# DCTCXO.net
KiCad netlist of a schematic drawn in Altium Designer
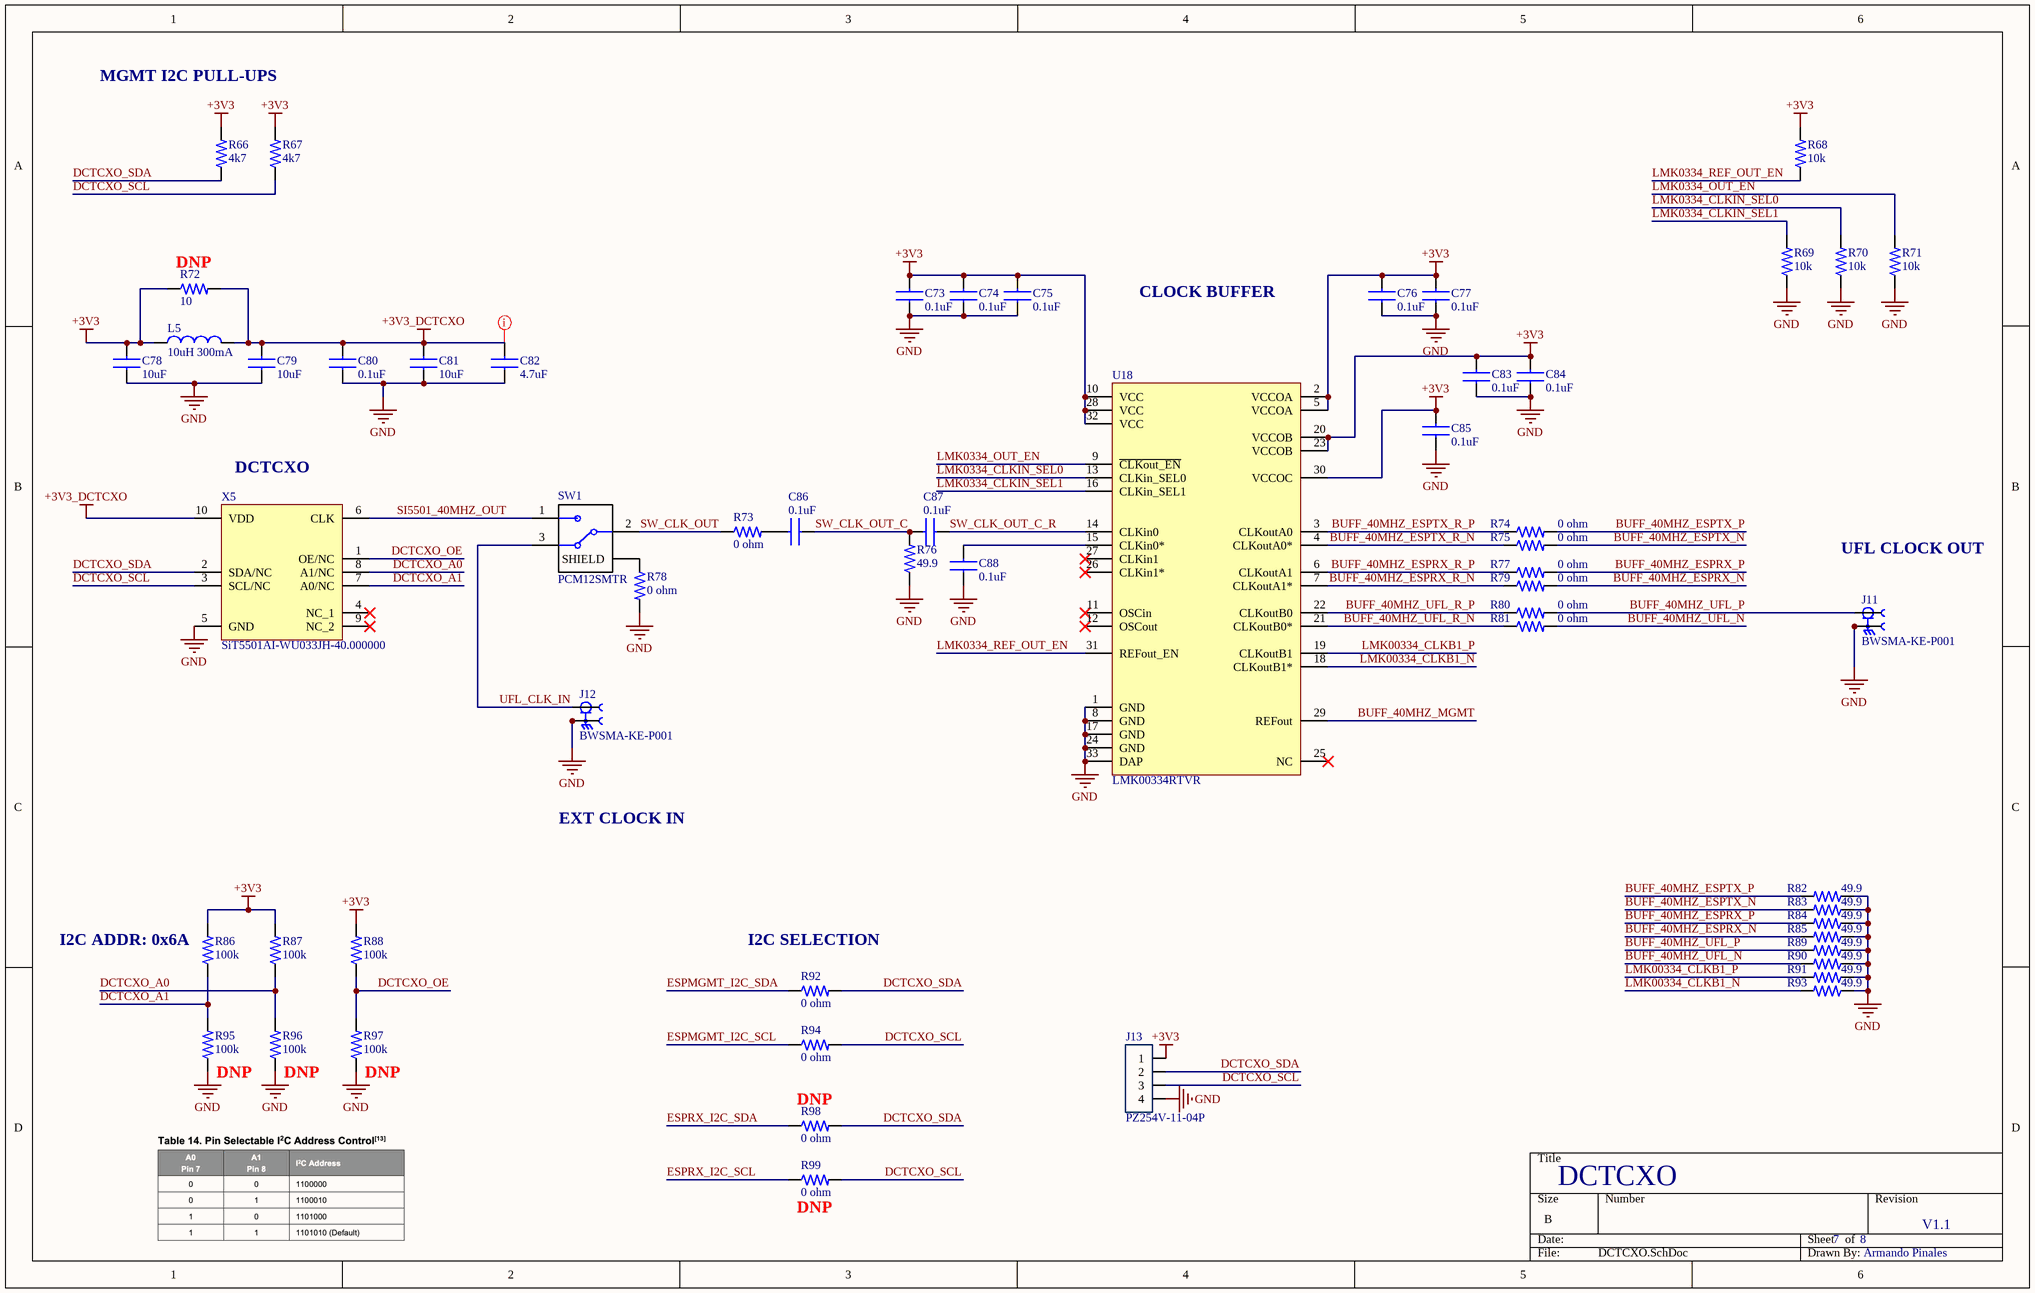
[diagram p0: DCTCXO.SchDoc]

(export (version "E")
  (design (tool "Eeschema 10.0.6"))
  (components
    (comp (ref "C73")
      (value "0.1uF")
      (footprint "CAP_0402")
      (description "Cap Ceramic 0.1uF 16V X7R 10% SMD 0402 125C Paper T/R")
      (fields
        (field (name "MANUFACTURER") "Murata")
        (field (name "MANUFACTURER PART NUMBER") "GCM155R71C104KA55J")
      )
      (libsource (lib "LotusSound") (part "CAP_GCM155R71C104KA55J"))
    )
    (comp (ref "C74")
      (value "0.1uF")
      (footprint "CAP_0402")
      (description "Cap Ceramic 0.1uF 16V X7R 10% SMD 0402 125C Paper T/R")
      (fields
        (field (name "MANUFACTURER") "Murata")
        (field (name "MANUFACTURER PART NUMBER") "GCM155R71C104KA55J")
      )
      (libsource (lib "LotusSound") (part "CAP_GCM155R71C104KA55J"))
    )
    (comp (ref "C75")
      (value "0.1uF")
      (footprint "CAP_0402")
      (description "Cap Ceramic 0.1uF 16V X7R 10% SMD 0402 125C Paper T/R")
      (fields
        (field (name "MANUFACTURER") "Murata")
        (field (name "MANUFACTURER PART NUMBER") "GCM155R71C104KA55J")
      )
      (libsource (lib "LotusSound") (part "CAP_GCM155R71C104KA55J"))
    )
    (comp (ref "C76")
      (value "0.1uF")
      (footprint "CAP_0402")
      (description "Cap Ceramic 0.1uF 16V X7R 10% SMD 0402 125C Paper T/R")
      (fields
        (field (name "MANUFACTURER") "Murata")
        (field (name "MANUFACTURER PART NUMBER") "GCM155R71C104KA55J")
      )
      (libsource (lib "LotusSound") (part "CAP_GCM155R71C104KA55J"))
    )
    (comp (ref "C77")
      (value "0.1uF")
      (footprint "CAP_0402")
      (description "Cap Ceramic 0.1uF 16V X7R 10% SMD 0402 125C Paper T/R")
      (fields
        (field (name "MANUFACTURER") "Murata")
        (field (name "MANUFACTURER PART NUMBER") "GCM155R71C104KA55J")
      )
      (libsource (lib "LotusSound") (part "CAP_GCM155R71C104KA55J"))
    )
    (comp (ref "C78")
      (value "10uF")
      (footprint "CAP_0402")
      (description "Cap Ceramic 10uF 6.3V X5R 20% SMD 0402 85°C Paper T/R")
      (fields
        (field (name "MANUFACTURER") "Samsung")
        (field (name "MANUFACTURER PART NUMBER") "CL05A106MQ5NUNC")
      )
      (libsource (lib "LotusSound") (part "CAP_CL05A106MQ5NUNC"))
    )
    (comp (ref "C79")
      (value "10uF")
      (footprint "CAP_0402")
      (description "Cap Ceramic 10uF 6.3V X5R 20% SMD 0402 85°C Paper T/R")
      (fields
        (field (name "MANUFACTURER") "Samsung")
        (field (name "MANUFACTURER PART NUMBER") "CL05A106MQ5NUNC")
      )
      (libsource (lib "LotusSound") (part "CAP_CL05A106MQ5NUNC"))
    )
    (comp (ref "C80")
      (value "0.1uF")
      (footprint "CAP_0402")
      (description "Cap Ceramic 0.1uF 16V X7R 10% SMD 0402 125C Paper T/R")
      (fields
        (field (name "MANUFACTURER") "Murata")
        (field (name "MANUFACTURER PART NUMBER") "GCM155R71C104KA55J")
      )
      (libsource (lib "LotusSound") (part "CAP_GCM155R71C104KA55J"))
    )
    (comp (ref "C81")
      (value "10uF")
      (footprint "CAP_0402")
      (description "Cap Ceramic 10uF 6.3V X5R 20% SMD 0402 85°C Paper T/R")
      (fields
        (field (name "MANUFACTURER") "Samsung")
        (field (name "MANUFACTURER PART NUMBER") "CL05A106MQ5NUNC")
      )
      (libsource (lib "LotusSound") (part "CAP_CL05A106MQ5NUNC"))
    )
    (comp (ref "C82")
      (value "4.7uF")
      (footprint "CAP_0402")
      (description "Multilayer Ceramic Capacitors MLCC - SMD/SMT 4.7uF 10V X5R +/-20% 0402 Gen Purp")
      (fields
        (field (name "MANUFACTURER") "Taiyo Yuden")
        (field (name "MANUFACTURER PART NUMBER") "LMK105BBJ475MVLF")
      )
      (libsource (lib "LotusSound") (part "CAP_LMK105BBJ475MVLF"))
    )
    (comp (ref "C83")
      (value "0.1uF")
      (footprint "CAP_0402")
      (description "Cap Ceramic 0.1uF 16V X7R 10% SMD 0402 125C Paper T/R")
      (fields
        (field (name "MANUFACTURER") "Murata")
        (field (name "MANUFACTURER PART NUMBER") "GCM155R71C104KA55J")
      )
      (libsource (lib "LotusSound") (part "CAP_GCM155R71C104KA55J"))
    )
    (comp (ref "C84")
      (value "0.1uF")
      (footprint "CAP_0402")
      (description "Cap Ceramic 0.1uF 16V X7R 10% SMD 0402 125C Paper T/R")
      (fields
        (field (name "MANUFACTURER") "Murata")
        (field (name "MANUFACTURER PART NUMBER") "GCM155R71C104KA55J")
      )
      (libsource (lib "LotusSound") (part "CAP_GCM155R71C104KA55J"))
    )
    (comp (ref "C85")
      (value "0.1uF")
      (footprint "CAP_0402")
      (description "Cap Ceramic 0.1uF 16V X7R 10% SMD 0402 125C Paper T/R")
      (fields
        (field (name "MANUFACTURER") "Murata")
        (field (name "MANUFACTURER PART NUMBER") "GCM155R71C104KA55J")
      )
      (libsource (lib "LotusSound") (part "CAP_GCM155R71C104KA55J"))
    )
    (comp (ref "C86")
      (value "0.1uF")
      (footprint "CAP_0402")
      (description "Cap Ceramic 0.1uF 16V X7R 10% SMD 0402 125C Paper T/R")
      (fields
        (field (name "MANUFACTURER") "Murata")
        (field (name "MANUFACTURER PART NUMBER") "GCM155R71C104KA55J")
      )
      (libsource (lib "LotusSound") (part "CAP_GCM155R71C104KA55J"))
    )
    (comp (ref "C87")
      (value "0.1uF")
      (footprint "CAP_0402")
      (description "Cap Ceramic 0.1uF 16V X7R 10% SMD 0402 125C Paper T/R")
      (fields
        (field (name "MANUFACTURER") "Murata")
        (field (name "MANUFACTURER PART NUMBER") "GCM155R71C104KA55J")
      )
      (libsource (lib "LotusSound") (part "CAP_GCM155R71C104KA55J"))
    )
    (comp (ref "C88")
      (value "0.1uF")
      (footprint "CAP_0402")
      (description "Cap Ceramic 0.1uF 16V X7R 10% SMD 0402 125C Paper T/R")
      (fields
        (field (name "MANUFACTURER") "Murata")
        (field (name "MANUFACTURER PART NUMBER") "GCM155R71C104KA55J")
      )
      (libsource (lib "LotusSound") (part "CAP_GCM155R71C104KA55J"))
    )
    (comp (ref "J11")
      (value "BWSMA-KE-P001")
      (footprint "CONN_BWSMA-KE-P001")
      (description "0-12.4GHz 50Ω 335V 直插偏脚")
      (fields (field (name "MANUFACTURER") "BAT Wireless"))
      (libsource (lib "LotusSound") (part "CONN_BWSMA-KE-P001"))
    )
    (comp (ref "J12")
      (value "BWSMA-KE-P001")
      (footprint "CONN_BWSMA-KE-P001")
      (description "0-12.4GHz 50Ω 335V 直插偏脚")
      (fields (field (name "MANUFACTURER") "BAT Wireless"))
      (libsource (lib "LotusSound") (part "CONN_BWSMA-KE-P001"))
    )
    (comp (ref "J13")
      (value "PZ254V-11-04P")
      (footprint "CONN_4_PIN_M_100MIL")
      (description "单排排针 间距2.54mm 4pin 直插")
      (fields (field (name "MANUFACTURER") "XFCN"))
      (libsource (lib "LotusSound") (part "CONN_4_PIN_MALE_PZ254V-11-04P"))
    )
    (comp (ref "L5")
      (value "10uH 300mA")
      (footprint "L_490-LQM18DN100M70LCT-ND")
      (description "Inductor, 10Uh, 0.3A, Multilayer Rohs Compliant: Yes")
      (fields
        (field (name "MANUFACTURER") "Murata")
        (field (name "MANUFACTURER PART NUMBER") "LQM18DN100M70L")
      )
      (libsource (lib "LotusSound") (part "L_LQM18DN100M70L"))
    )
    (comp (ref "R66")
      (value "4k7")
      (footprint "RES_0402")
      (description "Res General Purpose Thick Film 0402 4.7K Ohm 5% 1/16W ±100ppm/°C Molded SMD Paper T/R")
      (fields
        (field (name "MANUFACTURER") "Yageo")
        (field (name "MANUFACTURER PART NUMBER") "RC0402JR-074K7L")
      )
      (libsource (lib "LotusSound") (part "RES_RC0402JR-074K7L"))
    )
    (comp (ref "R67")
      (value "4k7")
      (footprint "RES_0402")
      (description "Res General Purpose Thick Film 0402 4.7K Ohm 5% 1/16W ±100ppm/°C Molded SMD Paper T/R")
      (fields
        (field (name "MANUFACTURER") "Yageo")
        (field (name "MANUFACTURER PART NUMBER") "RC0402JR-074K7L")
      )
      (libsource (lib "LotusSound") (part "RES_RC0402JR-074K7L"))
    )
    (comp (ref "R68")
      (value "10k")
      (footprint "RES_0402")
      (description "RES SMD 10K OHM 1% 1/16W 0402")
      (fields
        (field (name "MANUFACTURER") "Yageo")
        (field (name "MANUFACTURER PART NUMBER") "AC0402FR-0710KL")
      )
      (libsource (lib "LotusSound") (part "RES_AC0402FR-0710KL"))
    )
    (comp (ref "R69")
      (value "10k")
      (footprint "RES_0402")
      (description "RES SMD 10K OHM 1% 1/16W 0402")
      (fields
        (field (name "MANUFACTURER") "Yageo")
        (field (name "MANUFACTURER PART NUMBER") "AC0402FR-0710KL")
      )
      (libsource (lib "LotusSound") (part "RES_AC0402FR-0710KL"))
    )
    (comp (ref "R70")
      (value "10k")
      (footprint "RES_0402")
      (description "RES SMD 10K OHM 1% 1/16W 0402")
      (fields
        (field (name "MANUFACTURER") "Yageo")
        (field (name "MANUFACTURER PART NUMBER") "AC0402FR-0710KL")
      )
      (libsource (lib "LotusSound") (part "RES_AC0402FR-0710KL"))
    )
    (comp (ref "R71")
      (value "10k")
      (footprint "RES_0402")
      (description "RES SMD 10K OHM 1% 1/16W 0402")
      (fields
        (field (name "MANUFACTURER") "Yageo")
        (field (name "MANUFACTURER PART NUMBER") "AC0402FR-0710KL")
      )
      (libsource (lib "LotusSound") (part "RES_AC0402FR-0710KL"))
    )
    (comp (ref "R72")
      (value "10")
      (footprint "RES_0402")
      (description "Res General Purpose Thick Film 0402 10 Ohm 1% 1/16W ±200ppm/°C Molded SMD Paper T/R")
      (fields
        (field (name "MANUFACTURER") "Yageo")
        (field (name "MANUFACTURER PART NUMBER") "RC0402FR-0710RL")
      )
      (libsource (lib "LotusSound") (part "RES_RC0402FR-0710RL"))
    )
    (comp (ref "R73")
      (value "0 ohm")
      (footprint "RES_0402")
      (description "RES SMD 0 OHM JUMPER 1/16W 0402")
      (fields
        (field (name "MANUFACTURER") "Yageo")
        (field (name "MANUFACTURER PART NUMBER") "RC0402JR-070RL")
      )
      (libsource (lib "LotusSound") (part "RES_RC0402JR-070RL"))
    )
    (comp (ref "R74")
      (value "0 ohm")
      (footprint "RES_0402")
      (description "RES SMD 0 OHM JUMPER 1/16W 0402")
      (fields
        (field (name "MANUFACTURER") "Yageo")
        (field (name "MANUFACTURER PART NUMBER") "RC0402JR-070RL")
      )
      (libsource (lib "LotusSound") (part "RES_RC0402JR-070RL"))
    )
    (comp (ref "R75")
      (value "0 ohm")
      (footprint "RES_0402")
      (description "RES SMD 0 OHM JUMPER 1/16W 0402")
      (fields
        (field (name "MANUFACTURER") "Yageo")
        (field (name "MANUFACTURER PART NUMBER") "RC0402JR-070RL")
      )
      (libsource (lib "LotusSound") (part "RES_RC0402JR-070RL"))
    )
    (comp (ref "R76")
      (value "49.9")
      (footprint "RES_0402")
      (description "Res General Purpose Thick Film 0402 49.9 Ohm 1% 1/16W ±100ppm/°C Molded SMD Paper T/R")
      (fields
        (field (name "MANUFACTURER") "Yageo")
        (field (name "MANUFACTURER PART NUMBER") "RC0402FR-0749R9L")
      )
      (libsource (lib "LotusSound") (part "RES_RC0402FR-0749R9L"))
    )
    (comp (ref "R77")
      (value "0 ohm")
      (footprint "RES_0402")
      (description "RES SMD 0 OHM JUMPER 1/16W 0402")
      (fields
        (field (name "MANUFACTURER") "Yageo")
        (field (name "MANUFACTURER PART NUMBER") "RC0402JR-070RL")
      )
      (libsource (lib "LotusSound") (part "RES_RC0402JR-070RL"))
    )
    (comp (ref "R78")
      (value "0 ohm")
      (footprint "RES_0402")
      (description "RES SMD 0 OHM JUMPER 1/16W 0402")
      (fields
        (field (name "MANUFACTURER") "Yageo")
        (field (name "MANUFACTURER PART NUMBER") "RC0402JR-070RL")
      )
      (libsource (lib "LotusSound") (part "RES_RC0402JR-070RL"))
    )
    (comp (ref "R79")
      (value "0 ohm")
      (footprint "RES_0402")
      (description "RES SMD 0 OHM JUMPER 1/16W 0402")
      (fields
        (field (name "MANUFACTURER") "Yageo")
        (field (name "MANUFACTURER PART NUMBER") "RC0402JR-070RL")
      )
      (libsource (lib "LotusSound") (part "RES_RC0402JR-070RL"))
    )
    (comp (ref "R80")
      (value "0 ohm")
      (footprint "RES_0402")
      (description "RES SMD 0 OHM JUMPER 1/16W 0402")
      (fields
        (field (name "MANUFACTURER") "Yageo")
        (field (name "MANUFACTURER PART NUMBER") "RC0402JR-070RL")
      )
      (libsource (lib "LotusSound") (part "RES_RC0402JR-070RL"))
    )
    (comp (ref "R81")
      (value "0 ohm")
      (footprint "RES_0402")
      (description "RES SMD 0 OHM JUMPER 1/16W 0402")
      (fields
        (field (name "MANUFACTURER") "Yageo")
        (field (name "MANUFACTURER PART NUMBER") "RC0402JR-070RL")
      )
      (libsource (lib "LotusSound") (part "RES_RC0402JR-070RL"))
    )
    (comp (ref "R82")
      (value "49.9")
      (footprint "RES_0402")
      (description "Res General Purpose Thick Film 0402 49.9 Ohm 1% 1/16W ±100ppm/°C Molded SMD Paper T/R")
      (fields
        (field (name "MANUFACTURER") "Yageo")
        (field (name "MANUFACTURER PART NUMBER") "RC0402FR-0749R9L")
      )
      (libsource (lib "LotusSound") (part "RES_RC0402FR-0749R9L"))
    )
    (comp (ref "R83")
      (value "49.9")
      (footprint "RES_0402")
      (description "Res General Purpose Thick Film 0402 49.9 Ohm 1% 1/16W ±100ppm/°C Molded SMD Paper T/R")
      (fields
        (field (name "MANUFACTURER") "Yageo")
        (field (name "MANUFACTURER PART NUMBER") "RC0402FR-0749R9L")
      )
      (libsource (lib "LotusSound") (part "RES_RC0402FR-0749R9L"))
    )
    (comp (ref "R84")
      (value "49.9")
      (footprint "RES_0402")
      (description "Res General Purpose Thick Film 0402 49.9 Ohm 1% 1/16W ±100ppm/°C Molded SMD Paper T/R")
      (fields
        (field (name "MANUFACTURER") "Yageo")
        (field (name "MANUFACTURER PART NUMBER") "RC0402FR-0749R9L")
      )
      (libsource (lib "LotusSound") (part "RES_RC0402FR-0749R9L"))
    )
    (comp (ref "R85")
      (value "49.9")
      (footprint "RES_0402")
      (description "Res General Purpose Thick Film 0402 49.9 Ohm 1% 1/16W ±100ppm/°C Molded SMD Paper T/R")
      (fields
        (field (name "MANUFACTURER") "Yageo")
        (field (name "MANUFACTURER PART NUMBER") "RC0402FR-0749R9L")
      )
      (libsource (lib "LotusSound") (part "RES_RC0402FR-0749R9L"))
    )
    (comp (ref "R86")
      (value "100k")
      (footprint "RES_0402")
      (description "Res Thick Film 0402 100K Ohm 1% 1/16W ±100ppm/°C Molded SMD Paper T/R")
      (fields
        (field (name "MANUFACTURER") "Vishay")
        (field (name "MANUFACTURER PART NUMBER") "CRCW0402100KFKED")
      )
      (libsource (lib "LotusSound") (part "RES_CRCW0402100KFKED"))
    )
    (comp (ref "R87")
      (value "100k")
      (footprint "RES_0402")
      (description "Res Thick Film 0402 100K Ohm 1% 1/16W ±100ppm/°C Molded SMD Paper T/R")
      (fields
        (field (name "MANUFACTURER") "Vishay")
        (field (name "MANUFACTURER PART NUMBER") "CRCW0402100KFKED")
      )
      (libsource (lib "LotusSound") (part "RES_CRCW0402100KFKED"))
    )
    (comp (ref "R88")
      (value "100k")
      (footprint "RES_0402")
      (description "Res Thick Film 0402 100K Ohm 1% 1/16W ±100ppm/°C Molded SMD Paper T/R")
      (fields
        (field (name "MANUFACTURER") "Vishay")
        (field (name "MANUFACTURER PART NUMBER") "CRCW0402100KFKED")
      )
      (libsource (lib "LotusSound") (part "RES_CRCW0402100KFKED"))
    )
    (comp (ref "R89")
      (value "49.9")
      (footprint "RES_0402")
      (description "Res General Purpose Thick Film 0402 49.9 Ohm 1% 1/16W ±100ppm/°C Molded SMD Paper T/R")
      (fields
        (field (name "MANUFACTURER") "Yageo")
        (field (name "MANUFACTURER PART NUMBER") "RC0402FR-0749R9L")
      )
      (libsource (lib "LotusSound") (part "RES_RC0402FR-0749R9L"))
    )
    (comp (ref "R90")
      (value "49.9")
      (footprint "RES_0402")
      (description "Res General Purpose Thick Film 0402 49.9 Ohm 1% 1/16W ±100ppm/°C Molded SMD Paper T/R")
      (fields
        (field (name "MANUFACTURER") "Yageo")
        (field (name "MANUFACTURER PART NUMBER") "RC0402FR-0749R9L")
      )
      (libsource (lib "LotusSound") (part "RES_RC0402FR-0749R9L"))
    )
    (comp (ref "R91")
      (value "49.9")
      (footprint "RES_0402")
      (description "Res General Purpose Thick Film 0402 49.9 Ohm 1% 1/16W ±100ppm/°C Molded SMD Paper T/R")
      (fields
        (field (name "MANUFACTURER") "Yageo")
        (field (name "MANUFACTURER PART NUMBER") "RC0402FR-0749R9L")
      )
      (libsource (lib "LotusSound") (part "RES_RC0402FR-0749R9L"))
    )
    (comp (ref "R92")
      (value "0 ohm")
      (footprint "RES_0402")
      (description "RES SMD 0 OHM JUMPER 1/16W 0402")
      (fields
        (field (name "MANUFACTURER") "Yageo")
        (field (name "MANUFACTURER PART NUMBER") "RC0402JR-070RL")
      )
      (libsource (lib "LotusSound") (part "RES_RC0402JR-070RL"))
    )
    (comp (ref "R93")
      (value "49.9")
      (footprint "RES_0402")
      (description "Res General Purpose Thick Film 0402 49.9 Ohm 1% 1/16W ±100ppm/°C Molded SMD Paper T/R")
      (fields
        (field (name "MANUFACTURER") "Yageo")
        (field (name "MANUFACTURER PART NUMBER") "RC0402FR-0749R9L")
      )
      (libsource (lib "LotusSound") (part "RES_RC0402FR-0749R9L"))
    )
    (comp (ref "R94")
      (value "0 ohm")
      (footprint "RES_0402")
      (description "RES SMD 0 OHM JUMPER 1/16W 0402")
      (fields
        (field (name "MANUFACTURER") "Yageo")
        (field (name "MANUFACTURER PART NUMBER") "RC0402JR-070RL")
      )
      (libsource (lib "LotusSound") (part "RES_RC0402JR-070RL"))
    )
    (comp (ref "R95")
      (value "100k")
      (footprint "RES_0402")
      (description "Res Thick Film 0402 100K Ohm 1% 1/16W ±100ppm/°C Molded SMD Paper T/R")
      (fields
        (field (name "MANUFACTURER") "Vishay")
        (field (name "MANUFACTURER PART NUMBER") "CRCW0402100KFKED")
      )
      (libsource (lib "LotusSound") (part "RES_CRCW0402100KFKED"))
    )
    (comp (ref "R96")
      (value "100k")
      (footprint "RES_0402")
      (description "Res Thick Film 0402 100K Ohm 1% 1/16W ±100ppm/°C Molded SMD Paper T/R")
      (fields
        (field (name "MANUFACTURER") "Vishay")
        (field (name "MANUFACTURER PART NUMBER") "CRCW0402100KFKED")
      )
      (libsource (lib "LotusSound") (part "RES_CRCW0402100KFKED"))
    )
    (comp (ref "R97")
      (value "100k")
      (footprint "RES_0402")
      (description "Res Thick Film 0402 100K Ohm 1% 1/16W ±100ppm/°C Molded SMD Paper T/R")
      (fields
        (field (name "MANUFACTURER") "Vishay")
        (field (name "MANUFACTURER PART NUMBER") "CRCW0402100KFKED")
      )
      (libsource (lib "LotusSound") (part "RES_CRCW0402100KFKED"))
    )
    (comp (ref "R98")
      (value "0 ohm")
      (footprint "RES_0402")
      (description "RES SMD 0 OHM JUMPER 1/16W 0402")
      (fields
        (field (name "MANUFACTURER") "Yageo")
        (field (name "MANUFACTURER PART NUMBER") "RC0402JR-070RL")
      )
      (libsource (lib "LotusSound") (part "RES_RC0402JR-070RL"))
    )
    (comp (ref "R99")
      (value "0 ohm")
      (footprint "RES_0402")
      (description "RES SMD 0 OHM JUMPER 1/16W 0402")
      (fields
        (field (name "MANUFACTURER") "Yageo")
        (field (name "MANUFACTURER PART NUMBER") "RC0402JR-070RL")
      )
      (libsource (lib "LotusSound") (part "RES_RC0402JR-070RL"))
    )
    (comp (ref "SW1")
      (value "PCM12SMTR")
      (footprint "SW_PCM12SMTR")
      (description "Slide Switch SPDT Surface Mount, Right Angle")
      (fields (field (name "MF") "C&K") (field (name "DIGI-KEY_PART_NUMBER") "401-2016-1-ND"))
      (libsource (lib "LotusSound") (part "SW_PCM12SMTR"))
    )
    (comp (ref "U18")
      (value "LMK00334RTVR")
      (footprint "IC_LMK00334RTVR")
      (description "4-output PCIe Gen1/Gen2/Gen3/Gen4 clock buffer and level translator 32-WQFN -40 to 85")
      (fields (field (name "MANUFACTURER") "Texas Instruments"))
      (libsource (lib "LotusSound") (part "IC_LMK00334RTVR"))
    )
    (comp (ref "X5")
      (value "SiT5501AI-WU033JH-40.000000")
      (footprint "XTAL_SiT5501_70x50")
      (description "1 MHz  60 MHz, Elite X Stratum 3E Precision Oscillator")
      (libsource (lib "LotusSound") (part "XTAL_SIT5501AI-WUG33JT-10.000000"))
    )
  )
  (nets
    (net (code "1") (name "+3V3") (class "Default")
      (node (ref "C73") (pin "2") (pinfunction "2_2") (pintype "passive"))
      (node (ref "C74") (pin "2") (pinfunction "2_2") (pintype "passive"))
      (node (ref "C75") (pin "2") (pinfunction "2_2") (pintype "passive"))
      (node (ref "C76") (pin "2") (pinfunction "2_2") (pintype "passive"))
      (node (ref "C77") (pin "2") (pinfunction "2_2") (pintype "passive"))
      (node (ref "C78") (pin "2") (pinfunction "2_2") (pintype "passive"))
      (node (ref "C83") (pin "2") (pinfunction "2_2") (pintype "passive"))
      (node (ref "C84") (pin "2") (pinfunction "2_2") (pintype "passive"))
      (node (ref "C85") (pin "2") (pinfunction "2_2") (pintype "passive"))
      (node (ref "J13") (pin "1") (pinfunction "1_1") (pintype "passive"))
      (node (ref "L5") (pin "1") (pinfunction "1_1") (pintype "passive"))
      (node (ref "R66") (pin "2") (pinfunction "2_2") (pintype "passive"))
      (node (ref "R67") (pin "2") (pinfunction "2_2") (pintype "passive"))
      (node (ref "R68") (pin "2") (pinfunction "2_2") (pintype "passive"))
      (node (ref "R72") (pin "1") (pinfunction "1_1") (pintype "passive"))
      (node (ref "R86") (pin "2") (pinfunction "2_2") (pintype "passive"))
      (node (ref "R87") (pin "2") (pinfunction "2_2") (pintype "passive"))
      (node (ref "R88") (pin "2") (pinfunction "2_2") (pintype "passive"))
      (node (ref "U18") (pin "10") (pinfunction "VCC_10") (pintype "passive"))
      (node (ref "U18") (pin "2") (pinfunction "VCCOA_2") (pintype "passive"))
      (node (ref "U18") (pin "20") (pinfunction "VCCOB_20") (pintype "passive"))
      (node (ref "U18") (pin "23") (pinfunction "VCCOB_23") (pintype "passive"))
      (node (ref "U18") (pin "28") (pinfunction "VCC_28") (pintype "passive"))
      (node (ref "U18") (pin "30") (pinfunction "VCCOC_30") (pintype "passive"))
      (node (ref "U18") (pin "32") (pinfunction "VCC_32") (pintype "passive"))
      (node (ref "U18") (pin "5") (pinfunction "VCCOA_5") (pintype "passive"))
    )
    (net (code "2") (name "+3V3_DCTCXO") (class "Default")
      (node (ref "C79") (pin "2") (pinfunction "2_2") (pintype "passive"))
      (node (ref "C80") (pin "2") (pinfunction "2_2") (pintype "passive"))
      (node (ref "C81") (pin "2") (pinfunction "2_2") (pintype "passive"))
      (node (ref "C82") (pin "2") (pinfunction "2_2") (pintype "passive"))
      (node (ref "L5") (pin "2") (pinfunction "2_2") (pintype "passive"))
      (node (ref "R72") (pin "2") (pinfunction "2_2") (pintype "passive"))
      (node (ref "X5") (pin "10") (pinfunction "VDD_10") (pintype "passive"))
    )
    (net (code "3") (name "/BUFF_40MHZ_ESPRX_N") (class "Default")
      (node (ref "R79") (pin "2") (pinfunction "2_2") (pintype "passive"))
      (node (ref "R85") (pin "2") (pinfunction "2_2") (pintype "passive"))
    )
    (net (code "4") (name "/BUFF_40MHZ_ESPRX_P") (class "Default")
      (node (ref "R77") (pin "2") (pinfunction "2_2") (pintype "passive"))
      (node (ref "R84") (pin "2") (pinfunction "2_2") (pintype "passive"))
    )
    (net (code "5") (name "/BUFF_40MHZ_ESPRX_R_N") (class "Default")
      (node (ref "R79") (pin "1") (pinfunction "1_1") (pintype "passive"))
      (node (ref "U18") (pin "7") (pinfunction "CLKoutA1*_7") (pintype "passive"))
    )
    (net (code "6") (name "/BUFF_40MHZ_ESPRX_R_P") (class "Default")
      (node (ref "R77") (pin "1") (pinfunction "1_1") (pintype "passive"))
      (node (ref "U18") (pin "6") (pinfunction "CLKoutA1_6") (pintype "passive"))
    )
    (net (code "7") (name "/BUFF_40MHZ_ESPTX_N") (class "Default")
      (node (ref "R75") (pin "2") (pinfunction "2_2") (pintype "passive"))
      (node (ref "R83") (pin "2") (pinfunction "2_2") (pintype "passive"))
    )
    (net (code "8") (name "/BUFF_40MHZ_ESPTX_P") (class "Default")
      (node (ref "R74") (pin "2") (pinfunction "2_2") (pintype "passive"))
      (node (ref "R82") (pin "2") (pinfunction "2_2") (pintype "passive"))
    )
    (net (code "9") (name "/BUFF_40MHZ_ESPTX_R_N") (class "Default")
      (node (ref "R75") (pin "1") (pinfunction "1_1") (pintype "passive"))
      (node (ref "U18") (pin "4") (pinfunction "CLKoutA0*_4") (pintype "passive"))
    )
    (net (code "10") (name "/BUFF_40MHZ_ESPTX_R_P") (class "Default")
      (node (ref "R74") (pin "1") (pinfunction "1_1") (pintype "passive"))
      (node (ref "U18") (pin "3") (pinfunction "CLKoutA0_3") (pintype "passive"))
    )
    (net (code "11") (name "/BUFF_40MHZ_MGMT") (class "Default")
      (node (ref "U18") (pin "29") (pinfunction "REFout_29") (pintype "passive"))
    )
    (net (code "12") (name "/BUFF_40MHZ_UFL_N") (class "Default")
      (node (ref "R81") (pin "2") (pinfunction "2_2") (pintype "passive"))
      (node (ref "R90") (pin "2") (pinfunction "2_2") (pintype "passive"))
    )
    (net (code "13") (name "/BUFF_40MHZ_UFL_P") (class "Default")
      (node (ref "J11") (pin "1") (pinfunction "1_1") (pintype "passive"))
      (node (ref "R80") (pin "2") (pinfunction "2_2") (pintype "passive"))
      (node (ref "R89") (pin "2") (pinfunction "2_2") (pintype "passive"))
    )
    (net (code "14") (name "/BUFF_40MHZ_UFL_R_N") (class "Default")
      (node (ref "R81") (pin "1") (pinfunction "1_1") (pintype "passive"))
      (node (ref "U18") (pin "21") (pinfunction "CLKoutB0*_21") (pintype "passive"))
    )
    (net (code "15") (name "/BUFF_40MHZ_UFL_R_P") (class "Default")
      (node (ref "R80") (pin "1") (pinfunction "1_1") (pintype "passive"))
      (node (ref "U18") (pin "22") (pinfunction "CLKoutB0_22") (pintype "passive"))
    )
    (net (code "16") (name "/DCTCXO_A0") (class "Default")
      (node (ref "R87") (pin "1") (pinfunction "1_1") (pintype "passive"))
      (node (ref "R96") (pin "2") (pinfunction "2_2") (pintype "passive"))
      (node (ref "X5") (pin "8") (pinfunction "A1/NC_8") (pintype "passive"))
    )
    (net (code "17") (name "/DCTCXO_A1") (class "Default")
      (node (ref "R86") (pin "1") (pinfunction "1_1") (pintype "passive"))
      (node (ref "R95") (pin "2") (pinfunction "2_2") (pintype "passive"))
      (node (ref "X5") (pin "7") (pinfunction "A0/NC_7") (pintype "passive"))
    )
    (net (code "18") (name "/DCTCXO_OE") (class "Default")
      (node (ref "R88") (pin "1") (pinfunction "1_1") (pintype "passive"))
      (node (ref "R97") (pin "2") (pinfunction "2_2") (pintype "passive"))
      (node (ref "X5") (pin "1") (pinfunction "OE/NC_1") (pintype "passive"))
    )
    (net (code "19") (name "/DCTCXO_SCL") (class "Default")
      (node (ref "J13") (pin "3") (pinfunction "3_3") (pintype "passive"))
      (node (ref "R67") (pin "1") (pinfunction "1_1") (pintype "passive"))
      (node (ref "R94") (pin "2") (pinfunction "2_2") (pintype "passive"))
      (node (ref "R99") (pin "2") (pinfunction "2_2") (pintype "passive"))
      (node (ref "X5") (pin "3") (pinfunction "SCL/NC_3") (pintype "passive"))
    )
    (net (code "20") (name "/DCTCXO_SDA") (class "Default")
      (node (ref "J13") (pin "2") (pinfunction "2_2") (pintype "passive"))
      (node (ref "R66") (pin "1") (pinfunction "1_1") (pintype "passive"))
      (node (ref "R92") (pin "2") (pinfunction "2_2") (pintype "passive"))
      (node (ref "R98") (pin "2") (pinfunction "2_2") (pintype "passive"))
      (node (ref "X5") (pin "2") (pinfunction "SDA/NC_2") (pintype "passive"))
    )
    (net (code "21") (name "/ESPMGMT_I2C_SCL") (class "Default")
      (node (ref "R94") (pin "1") (pinfunction "1_1") (pintype "passive"))
    )
    (net (code "22") (name "/ESPMGMT_I2C_SDA") (class "Default")
      (node (ref "R92") (pin "1") (pinfunction "1_1") (pintype "passive"))
    )
    (net (code "23") (name "/ESPRX_I2C_SCL") (class "Default")
      (node (ref "R99") (pin "1") (pinfunction "1_1") (pintype "passive"))
    )
    (net (code "24") (name "/ESPRX_I2C_SDA") (class "Default")
      (node (ref "R98") (pin "1") (pinfunction "1_1") (pintype "passive"))
    )
    (net (code "25") (name "/LMK00334_CLKB1_N") (class "Default")
      (node (ref "R93") (pin "2") (pinfunction "2_2") (pintype "passive"))
      (node (ref "U18") (pin "18") (pinfunction "CLKoutB1*_18") (pintype "passive"))
    )
    (net (code "26") (name "/LMK00334_CLKB1_P") (class "Default")
      (node (ref "R91") (pin "2") (pinfunction "2_2") (pintype "passive"))
      (node (ref "U18") (pin "19") (pinfunction "CLKoutB1_19") (pintype "passive"))
    )
    (net (code "27") (name "/LMK0334_CLKIN_SEL0") (class "Default")
      (node (ref "R70") (pin "2") (pinfunction "2_2") (pintype "passive"))
      (node (ref "U18") (pin "13") (pinfunction "CLKin_SEL0_13") (pintype "passive"))
    )
    (net (code "28") (name "/LMK0334_CLKIN_SEL1") (class "Default")
      (node (ref "R69") (pin "2") (pinfunction "2_2") (pintype "passive"))
      (node (ref "U18") (pin "16") (pinfunction "CLKin_SEL1_16") (pintype "passive"))
    )
    (net (code "29") (name "/LMK0334_OUT_EN") (class "Default")
      (node (ref "R71") (pin "2") (pinfunction "2_2") (pintype "passive"))
      (node (ref "U18") (pin "9") (pinfunction "~{CLKout_EN}_9") (pintype "passive"))
    )
    (net (code "30") (name "/LMK0334_REF_OUT_EN") (class "Default")
      (node (ref "R68") (pin "1") (pinfunction "1_1") (pintype "passive"))
      (node (ref "U18") (pin "31") (pinfunction "REFout_EN_31") (pintype "passive"))
    )
    (net (code "31") (name "/SI5501_40MHZ_OUT") (class "Default")
      (node (ref "SW1") (pin "1") (pinfunction "1_1") (pintype "passive"))
      (node (ref "X5") (pin "6") (pinfunction "CLK_6") (pintype "passive"))
    )
    (net (code "32") (name "/SW_CLK_OUT") (class "Default")
      (node (ref "R73") (pin "1") (pinfunction "1_1") (pintype "passive"))
      (node (ref "SW1") (pin "2") (pinfunction "2_2") (pintype "passive"))
    )
    (net (code "33") (name "/SW_CLK_OUT_C") (class "Default")
      (node (ref "C86") (pin "1") (pinfunction "1_1") (pintype "passive"))
      (node (ref "C87") (pin "2") (pinfunction "2_2") (pintype "passive"))
      (node (ref "R76") (pin "2") (pinfunction "2_2") (pintype "passive"))
    )
    (net (code "34") (name "/SW_CLK_OUT_C_R") (class "Default")
      (node (ref "C87") (pin "1") (pinfunction "1_1") (pintype "passive"))
      (node (ref "U18") (pin "14") (pinfunction "CLKin0_14") (pintype "passive"))
    )
    (net (code "35") (name "/UFL_CLK_IN") (class "Default")
      (node (ref "J12") (pin "1") (pinfunction "1_1") (pintype "passive"))
      (node (ref "SW1") (pin "3") (pinfunction "3_3") (pintype "passive"))
    )
    (net (code "36") (name "GND") (class "Default")
      (node (ref "C73") (pin "1") (pinfunction "1_1") (pintype "passive"))
      (node (ref "C74") (pin "1") (pinfunction "1_1") (pintype "passive"))
      (node (ref "C75") (pin "1") (pinfunction "1_1") (pintype "passive"))
      (node (ref "C76") (pin "1") (pinfunction "1_1") (pintype "passive"))
      (node (ref "C77") (pin "1") (pinfunction "1_1") (pintype "passive"))
      (node (ref "C78") (pin "1") (pinfunction "1_1") (pintype "passive"))
      (node (ref "C79") (pin "1") (pinfunction "1_1") (pintype "passive"))
      (node (ref "C80") (pin "1") (pinfunction "1_1") (pintype "passive"))
      (node (ref "C81") (pin "1") (pinfunction "1_1") (pintype "passive"))
      (node (ref "C82") (pin "1") (pinfunction "1_1") (pintype "passive"))
      (node (ref "C83") (pin "1") (pinfunction "1_1") (pintype "passive"))
      (node (ref "C84") (pin "1") (pinfunction "1_1") (pintype "passive"))
      (node (ref "C85") (pin "1") (pinfunction "1_1") (pintype "passive"))
      (node (ref "C88") (pin "2") (pinfunction "2_2") (pintype "passive"))
      (node (ref "J11") (pin "2") (pinfunction "2_2") (pintype "passive"))
      (node (ref "J11") (pin "3") (pinfunction "3_3") (pintype "passive"))
      (node (ref "J11") (pin "4") (pinfunction "4_4") (pintype "passive"))
      (node (ref "J11") (pin "5") (pinfunction "5_5") (pintype "passive"))
      (node (ref "J12") (pin "2") (pinfunction "2_2") (pintype "passive"))
      (node (ref "J12") (pin "3") (pinfunction "3_3") (pintype "passive"))
      (node (ref "J12") (pin "4") (pinfunction "4_4") (pintype "passive"))
      (node (ref "J12") (pin "5") (pinfunction "5_5") (pintype "passive"))
      (node (ref "J13") (pin "4") (pinfunction "4_4") (pintype "passive"))
      (node (ref "R69") (pin "1") (pinfunction "1_1") (pintype "passive"))
      (node (ref "R70") (pin "1") (pinfunction "1_1") (pintype "passive"))
      (node (ref "R71") (pin "1") (pinfunction "1_1") (pintype "passive"))
      (node (ref "R76") (pin "1") (pinfunction "1_1") (pintype "passive"))
      (node (ref "R78") (pin "2") (pinfunction "2_2") (pintype "passive"))
      (node (ref "R82") (pin "1") (pinfunction "1_1") (pintype "passive"))
      (node (ref "R83") (pin "1") (pinfunction "1_1") (pintype "passive"))
      (node (ref "R84") (pin "1") (pinfunction "1_1") (pintype "passive"))
      (node (ref "R85") (pin "1") (pinfunction "1_1") (pintype "passive"))
      (node (ref "R89") (pin "1") (pinfunction "1_1") (pintype "passive"))
      (node (ref "R90") (pin "1") (pinfunction "1_1") (pintype "passive"))
      (node (ref "R91") (pin "1") (pinfunction "1_1") (pintype "passive"))
      (node (ref "R93") (pin "1") (pinfunction "1_1") (pintype "passive"))
      (node (ref "R95") (pin "1") (pinfunction "1_1") (pintype "passive"))
      (node (ref "R96") (pin "1") (pinfunction "1_1") (pintype "passive"))
      (node (ref "R97") (pin "1") (pinfunction "1_1") (pintype "passive"))
      (node (ref "U18") (pin "1") (pinfunction "GND_1") (pintype "passive"))
      (node (ref "U18") (pin "17") (pinfunction "GND_17") (pintype "passive"))
      (node (ref "U18") (pin "24") (pinfunction "GND_24") (pintype "passive"))
      (node (ref "U18") (pin "33") (pinfunction "DAP_33") (pintype "passive"))
      (node (ref "U18") (pin "8") (pinfunction "GND_8") (pintype "passive"))
      (node (ref "X5") (pin "5") (pinfunction "GND_5") (pintype "passive"))
    )
    (net (code "37") (name "Net-(C86-Pad2)") (class "Default")
      (node (ref "C86") (pin "2") (pinfunction "2_2") (pintype "passive"))
      (node (ref "R73") (pin "2") (pinfunction "2_2") (pintype "passive"))
    )
    (net (code "38") (name "Net-(SW1-SHIELD)") (class "Default")
      (node (ref "R78") (pin "1") (pinfunction "1_1") (pintype "passive"))
      (node (ref "SW1") (pin "S4") (pinfunction "SHIELD_S4") (pintype "passive"))
    )
    (net (code "39") (name "Net-(U18-CLKin0*)") (class "Default")
      (node (ref "C88") (pin "1") (pinfunction "1_1") (pintype "passive"))
      (node (ref "U18") (pin "15") (pinfunction "CLKin0*_15") (pintype "passive"))
    )
    (net (code "40") (name "unconnected-(U18-CLKin1*-Pad26)") (class "Default")
      (node (ref "U18") (pin "26") (pinfunction "CLKin1*_26") (pintype "passive+no_connect"))
    )
    (net (code "41") (name "unconnected-(U18-CLKin1-Pad27)") (class "Default")
      (node (ref "U18") (pin "27") (pinfunction "CLKin1_27") (pintype "passive+no_connect"))
    )
    (net (code "42") (name "unconnected-(U18-NC-Pad25)") (class "Default")
      (node (ref "U18") (pin "25") (pinfunction "NC_25") (pintype "passive+no_connect"))
    )
    (net (code "43") (name "unconnected-(U18-OSCin-Pad11)") (class "Default")
      (node (ref "U18") (pin "11") (pinfunction "OSCin_11") (pintype "passive+no_connect"))
    )
    (net (code "44") (name "unconnected-(U18-OSCout-Pad12)") (class "Default")
      (node (ref "U18") (pin "12") (pinfunction "OSCout_12") (pintype "passive+no_connect"))
    )
    (net (code "45") (name "unconnected-(X5-NC_1-Pad4)") (class "Default")
      (node (ref "X5") (pin "4") (pinfunction "NC_1_4") (pintype "passive+no_connect"))
    )
    (net (code "46") (name "unconnected-(X5-NC_2-Pad9)") (class "Default")
      (node (ref "X5") (pin "9") (pinfunction "NC_2_9") (pintype "passive+no_connect"))
    )
  )
)
